# untitled.net
KiCad netlist of a schematic drawn in EAGLE
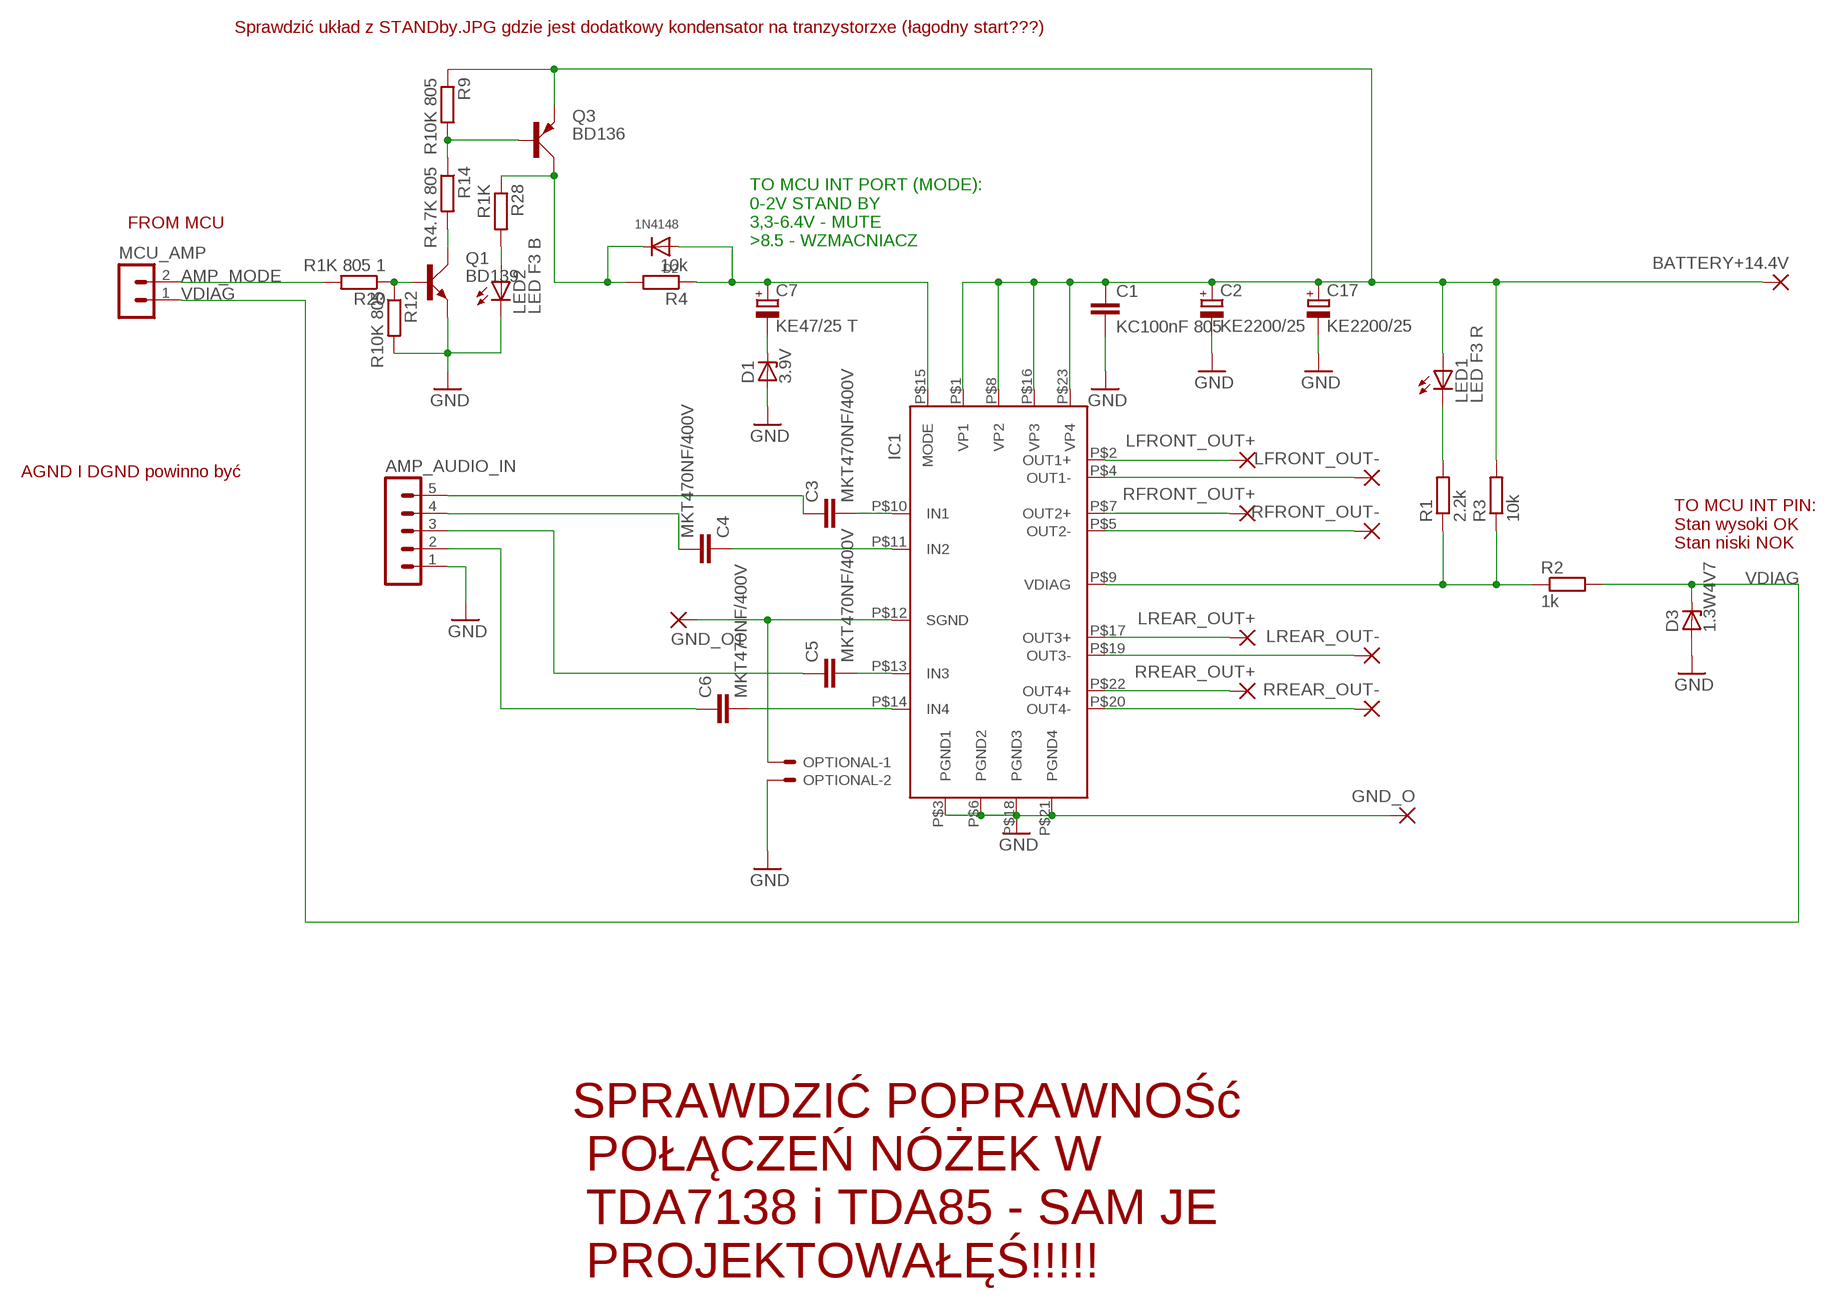
[diagram p0: schematic, sheet 1]

(export (version "E")
  (design (tool "Eeschema 10.0.6"))
  (components
    (comp (ref "AMP_AUDIO_IN")
      (value "MA05-1")
      (footprint "eagle-import:MA05-1")
      (fields (field (name "OC_FARNELL") "unknown") (field (name "OC_NEWARK") "unknown"))
      (libsource (lib "eagle-import") (part "MA05-1"))
    )
    (comp (ref "BATTERY+14.4V")
      (value "WIREPAD2,54/1,0")
      (footprint "eagle-import:2,54_1,0")
      (libsource (lib "eagle-import") (part "WIREPAD2,54/1,0"))
    )
    (comp (ref "C1")
      (value "KC100nF 805")
      (footprint "eagle-import:C0805")
      (libsource (lib "eagle-import") (part "C-EUC0805"))
    )
    (comp (ref "C2")
      (value "KE2200/25")
      (footprint "eagle-import:EB20D")
      (libsource (lib "eagle-import") (part "CPOL-EUE10-20"))
    )
    (comp (ref "C3")
      (value "MKT470NF/400V")
      (footprint "eagle-import:C025-024X044")
      (libsource (lib "eagle-import") (part "C-EU025-024X044"))
    )
    (comp (ref "C4")
      (value "MKT470NF/400V")
      (footprint "eagle-import:C025-024X044")
      (libsource (lib "eagle-import") (part "C-EU025-024X044"))
    )
    (comp (ref "C5")
      (value "MKT470NF/400V")
      (footprint "eagle-import:C025-024X044")
      (libsource (lib "eagle-import") (part "C-EU025-024X044"))
    )
    (comp (ref "C6")
      (value "MKT470NF/400V")
      (footprint "eagle-import:C025-024X044")
      (libsource (lib "eagle-import") (part "C-EU025-024X044"))
    )
    (comp (ref "C7")
      (value "KE47/25 T")
      (footprint "eagle-import:B45181A")
      (libsource (lib "eagle-import") (part "CPOL-EUB45181A"))
    )
    (comp (ref "C17")
      (value "KE2200/25")
      (footprint "eagle-import:EB20D")
      (libsource (lib "eagle-import") (part "CPOL-EUE10-20"))
    )
    (comp (ref "D1")
      (value "3.9V")
      (footprint "eagle-import:ZDIO-5")
      (libsource (lib "eagle-import") (part "ZENER-DIODEZD-5"))
    )
    (comp (ref "D2")
      (value "1N4148")
      (footprint "eagle-import:DO-1N4148")
      (libsource (lib "eagle-import") (part "DIODEDO-1N4148"))
    )
    (comp (ref "D3")
      (value "1.3W4V7")
      (footprint "eagle-import:ZDIO-5")
      (libsource (lib "eagle-import") (part "ZENER-DIODEZD-5"))
    )
    (comp (ref "GND_O")
      (value "WIREPAD2,54/1,0")
      (footprint "eagle-import:2,54_1,0")
      (libsource (lib "eagle-import") (part "WIREPAD2,54/1,0"))
    )
    (comp (ref "GND_O1")
      (value "WIREPAD2,54/1,0")
      (footprint "eagle-import:2,54_1,0")
      (libsource (lib "eagle-import") (part "WIREPAD2,54/1,0"))
    )
    (comp (ref "IC1")
      (value "TDA8571J")
      (footprint "eagle-import:SOT411-1")
      (libsource (lib "eagle-import") (part "TDA8571J"))
    )
    (comp (ref "LED1")
      (value "LED F3 R")
      (footprint "eagle-import:LED3MM")
      (libsource (lib "eagle-import") (part "LED3MM"))
    )
    (comp (ref "LED2")
      (value "LED F3 B")
      (footprint "eagle-import:LED3MM")
      (libsource (lib "eagle-import") (part "LED3MM"))
    )
    (comp (ref "LFRONT_OUT+")
      (value "WIREPAD2,54/1,0")
      (footprint "eagle-import:2,54_1,0")
      (libsource (lib "eagle-import") (part "WIREPAD2,54/1,0"))
    )
    (comp (ref "LFRONT_OUT-")
      (value "WIREPAD2,54/1,0")
      (footprint "eagle-import:2,54_1,0")
      (libsource (lib "eagle-import") (part "WIREPAD2,54/1,0"))
    )
    (comp (ref "LREAR_OUT+")
      (value "WIREPAD2,54/1,0")
      (footprint "eagle-import:2,54_1,0")
      (libsource (lib "eagle-import") (part "WIREPAD2,54/1,0"))
    )
    (comp (ref "LREAR_OUT-")
      (value "WIREPAD2,54/1,0")
      (footprint "eagle-import:2,54_1,0")
      (libsource (lib "eagle-import") (part "WIREPAD2,54/1,0"))
    )
    (comp (ref "MCU_AMP")
      (value "MA02-1")
      (footprint "eagle-import:MA02-1")
      (libsource (lib "eagle-import") (part "MA02-1"))
    )
    (comp (ref "OPTIONAL")
      (value "332-02")
      (footprint "eagle-import:332-02")
      (libsource (lib "eagle-import") (part "332-02"))
    )
    (comp (ref "Q1")
      (value "BD139")
      (footprint "eagle-import:TO126AV")
      (libsource (lib "eagle-import") (part "BD139"))
    )
    (comp (ref "Q3")
      (value "BD136")
      (footprint "eagle-import:TO126AV")
      (libsource (lib "eagle-import") (part "BD140"))
    )
    (comp (ref "R1")
      (value "2.2k")
      (footprint "eagle-import:0204_5")
      (libsource (lib "eagle-import") (part "R-EU_0204/5"))
    )
    (comp (ref "R2")
      (value "1k")
      (footprint "eagle-import:0204_5")
      (libsource (lib "eagle-import") (part "R-EU_0204/5"))
    )
    (comp (ref "R3")
      (value "10k")
      (footprint "eagle-import:0204_5")
      (libsource (lib "eagle-import") (part "R-EU_0204/5"))
    )
    (comp (ref "R4")
      (value "10k")
      (footprint "eagle-import:0204_5")
      (libsource (lib "eagle-import") (part "R-EU_0204/5"))
    )
    (comp (ref "R9")
      (value "R10K 805")
      (footprint "eagle-import:R0805")
      (libsource (lib "eagle-import") (part "R-EU_R0805"))
    )
    (comp (ref "R12")
      (value "R10K 805")
      (footprint "eagle-import:R0805")
      (libsource (lib "eagle-import") (part "R-EU_R0805"))
    )
    (comp (ref "R14")
      (value "R4.7K 805")
      (footprint "eagle-import:R0805")
      (libsource (lib "eagle-import") (part "R-EU_R0805"))
    )
    (comp (ref "R20")
      (value "R1K 805 1")
      (footprint "eagle-import:R0805")
      (libsource (lib "eagle-import") (part "R-EU_R0805"))
    )
    (comp (ref "R28")
      (value "R1K")
      (footprint "eagle-import:0204V")
      (libsource (lib "eagle-import") (part "R-EU_0204/2V"))
    )
    (comp (ref "RFRONT_OUT+")
      (value "WIREPAD2,54/1,0")
      (footprint "eagle-import:2,54_1,0")
      (libsource (lib "eagle-import") (part "WIREPAD2,54/1,0"))
    )
    (comp (ref "RFRONT_OUT-")
      (value "WIREPAD2,54/1,0")
      (footprint "eagle-import:2,54_1,0")
      (libsource (lib "eagle-import") (part "WIREPAD2,54/1,0"))
    )
    (comp (ref "RREAR_OUT+")
      (value "WIREPAD2,54/1,0")
      (footprint "eagle-import:2,54_1,0")
      (libsource (lib "eagle-import") (part "WIREPAD2,54/1,0"))
    )
    (comp (ref "RREAR_OUT-")
      (value "WIREPAD2,54/1,0")
      (footprint "eagle-import:2,54_1,0")
      (libsource (lib "eagle-import") (part "WIREPAD2,54/1,0"))
    )
  )
  (nets
    (net (code "1") (name "/AMP_MODE") (class "Default")
      (node (ref "MCU_AMP") (pin "2") (pinfunction "2_2") (pintype "passive"))
      (node (ref "R20") (pin "2") (pinfunction "2_2") (pintype "passive"))
    )
    (net (code "2") (name "/VDIAG") (class "Default")
      (node (ref "D3") (pin "C") (pinfunction "C_C") (pintype "passive"))
      (node (ref "MCU_AMP") (pin "1") (pinfunction "1_1") (pintype "passive"))
      (node (ref "R2") (pin "2") (pinfunction "2_2") (pintype "passive"))
    )
    (net (code "3") (name "GND") (class "Default")
      (node (ref "AMP_AUDIO_IN") (pin "1") (pinfunction "1_1") (pintype "passive"))
      (node (ref "C1") (pin "2") (pinfunction "2_2") (pintype "passive"))
      (node (ref "C17") (pin "-") (pinfunction "-_-") (pintype "passive"))
      (node (ref "C2") (pin "-") (pinfunction "-_-") (pintype "passive"))
      (node (ref "D1") (pin "A") (pinfunction "A_A") (pintype "passive"))
      (node (ref "D3") (pin "A") (pinfunction "A_A") (pintype "passive"))
      (node (ref "GND_O") (pin "1") (pinfunction "P_1") (pintype "passive"))
      (node (ref "IC1") (pin "P$18") (pinfunction "PGND3_P$18") (pintype "power_in"))
      (node (ref "IC1") (pin "P$21") (pinfunction "PGND4_P$21") (pintype "power_in"))
      (node (ref "IC1") (pin "P$3") (pinfunction "PGND1_P$3") (pintype "power_in"))
      (node (ref "IC1") (pin "P$6") (pinfunction "PGND2_P$6") (pintype "power_in"))
      (node (ref "LED2") (pin "K") (pinfunction "C_K") (pintype "passive"))
      (node (ref "OPTIONAL") (pin "2") (pinfunction "S_2") (pintype "passive"))
      (node (ref "Q1") (pin "E") (pinfunction "E_E") (pintype "passive"))
      (node (ref "R12") (pin "2") (pinfunction "2_2") (pintype "passive"))
    )
    (net (code "4") (name "Net-(AMP_AUDIO_IN-Pad2)") (class "Default")
      (node (ref "AMP_AUDIO_IN") (pin "2") (pinfunction "2_2") (pintype "passive"))
      (node (ref "C6") (pin "1") (pinfunction "1_1") (pintype "passive"))
    )
    (net (code "5") (name "Net-(AMP_AUDIO_IN-Pad3)") (class "Default")
      (node (ref "AMP_AUDIO_IN") (pin "3") (pinfunction "3_3") (pintype "passive"))
      (node (ref "C5") (pin "1") (pinfunction "1_1") (pintype "passive"))
    )
    (net (code "6") (name "Net-(AMP_AUDIO_IN-Pad4)") (class "Default")
      (node (ref "AMP_AUDIO_IN") (pin "4") (pinfunction "4_4") (pintype "passive"))
      (node (ref "C4") (pin "2") (pinfunction "2_2") (pintype "passive"))
    )
    (net (code "7") (name "Net-(AMP_AUDIO_IN-Pad5)") (class "Default")
      (node (ref "AMP_AUDIO_IN") (pin "5") (pinfunction "5_5") (pintype "passive"))
      (node (ref "C3") (pin "1") (pinfunction "1_1") (pintype "passive"))
    )
    (net (code "8") (name "Net-(BATTERY+14.4V-P)") (class "Default")
      (node (ref "BATTERY+14.4V") (pin "1") (pinfunction "P_1") (pintype "passive"))
      (node (ref "C1") (pin "1") (pinfunction "1_1") (pintype "passive"))
      (node (ref "C17") (pin "+") (pinfunction "+_+") (pintype "passive"))
      (node (ref "C2") (pin "+") (pinfunction "+_+") (pintype "passive"))
      (node (ref "IC1") (pin "P$1") (pinfunction "VP1_P$1") (pintype "power_in"))
      (node (ref "IC1") (pin "P$16") (pinfunction "VP3_P$16") (pintype "power_in"))
      (node (ref "IC1") (pin "P$23") (pinfunction "VP4_P$23") (pintype "power_in"))
      (node (ref "IC1") (pin "P$8") (pinfunction "VP2_P$8") (pintype "power_in"))
      (node (ref "LED1") (pin "A") (pinfunction "A_A") (pintype "passive"))
      (node (ref "Q3") (pin "E") (pinfunction "E_E") (pintype "passive"))
      (node (ref "R3") (pin "2") (pinfunction "2_2") (pintype "passive"))
      (node (ref "R9") (pin "1") (pinfunction "1_1") (pintype "passive"))
    )
    (net (code "9") (name "Net-(C7-Pad-)") (class "Default")
      (node (ref "C7") (pin "-") (pinfunction "-_-") (pintype "passive"))
      (node (ref "D1") (pin "C") (pinfunction "C_C") (pintype "passive"))
    )
    (net (code "10") (name "Net-(D2-PadC)") (class "Default")
      (node (ref "D2") (pin "C") (pinfunction "C_C") (pintype "passive"))
      (node (ref "Q3") (pin "C") (pinfunction "C_C") (pintype "passive"))
      (node (ref "R28") (pin "1") (pinfunction "1_1") (pintype "passive"))
      (node (ref "R4") (pin "2") (pinfunction "2_2") (pintype "passive"))
    )
    (net (code "11") (name "Net-(GND_O1-P)") (class "Default")
      (node (ref "GND_O1") (pin "1") (pinfunction "P_1") (pintype "passive"))
      (node (ref "IC1") (pin "P$12") (pinfunction "SGND_P$12") (pintype "power_in"))
      (node (ref "OPTIONAL") (pin "1") (pinfunction "S_1") (pintype "passive"))
    )
    (net (code "12") (name "Net-(IC1-IN1)") (class "Default")
      (node (ref "C3") (pin "2") (pinfunction "2_2") (pintype "passive"))
      (node (ref "IC1") (pin "P$10") (pinfunction "IN1_P$10") (pintype "input"))
    )
    (net (code "13") (name "Net-(IC1-IN2)") (class "Default")
      (node (ref "C4") (pin "1") (pinfunction "1_1") (pintype "passive"))
      (node (ref "IC1") (pin "P$11") (pinfunction "IN2_P$11") (pintype "input"))
    )
    (net (code "14") (name "Net-(IC1-IN3)") (class "Default")
      (node (ref "C5") (pin "2") (pinfunction "2_2") (pintype "passive"))
      (node (ref "IC1") (pin "P$13") (pinfunction "IN3_P$13") (pintype "input"))
    )
    (net (code "15") (name "Net-(IC1-IN4)") (class "Default")
      (node (ref "C6") (pin "2") (pinfunction "2_2") (pintype "passive"))
      (node (ref "IC1") (pin "P$14") (pinfunction "IN4_P$14") (pintype "input"))
    )
    (net (code "16") (name "Net-(IC1-MODE)") (class "Default")
      (node (ref "C7") (pin "+") (pinfunction "+_+") (pintype "passive"))
      (node (ref "D2") (pin "A") (pinfunction "A_A") (pintype "passive"))
      (node (ref "IC1") (pin "P$15") (pinfunction "MODE_P$15") (pintype "bidirectional"))
      (node (ref "R4") (pin "1") (pinfunction "1_1") (pintype "passive"))
    )
    (net (code "17") (name "Net-(IC1-OUT1+)") (class "Default")
      (node (ref "IC1") (pin "P$2") (pinfunction "OUT1+_P$2") (pintype "output"))
      (node (ref "LFRONT_OUT+") (pin "1") (pinfunction "P_1") (pintype "passive"))
    )
    (net (code "18") (name "Net-(IC1-OUT1-)") (class "Default")
      (node (ref "IC1") (pin "P$4") (pinfunction "OUT1-_P$4") (pintype "output"))
      (node (ref "LFRONT_OUT-") (pin "1") (pinfunction "P_1") (pintype "passive"))
    )
    (net (code "19") (name "Net-(IC1-OUT2+)") (class "Default")
      (node (ref "IC1") (pin "P$7") (pinfunction "OUT2+_P$7") (pintype "output"))
      (node (ref "RFRONT_OUT+") (pin "1") (pinfunction "P_1") (pintype "passive"))
    )
    (net (code "20") (name "Net-(IC1-OUT2-)") (class "Default")
      (node (ref "IC1") (pin "P$5") (pinfunction "OUT2-_P$5") (pintype "output"))
      (node (ref "RFRONT_OUT-") (pin "1") (pinfunction "P_1") (pintype "passive"))
    )
    (net (code "21") (name "Net-(IC1-OUT3+)") (class "Default")
      (node (ref "IC1") (pin "P$17") (pinfunction "OUT3+_P$17") (pintype "output"))
      (node (ref "LREAR_OUT+") (pin "1") (pinfunction "P_1") (pintype "passive"))
    )
    (net (code "22") (name "Net-(IC1-OUT3-)") (class "Default")
      (node (ref "IC1") (pin "P$19") (pinfunction "OUT3-_P$19") (pintype "output"))
      (node (ref "LREAR_OUT-") (pin "1") (pinfunction "P_1") (pintype "passive"))
    )
    (net (code "23") (name "Net-(IC1-OUT4+)") (class "Default")
      (node (ref "IC1") (pin "P$22") (pinfunction "OUT4+_P$22") (pintype "output"))
      (node (ref "RREAR_OUT+") (pin "1") (pinfunction "P_1") (pintype "passive"))
    )
    (net (code "24") (name "Net-(IC1-OUT4-)") (class "Default")
      (node (ref "IC1") (pin "P$20") (pinfunction "OUT4-_P$20") (pintype "output"))
      (node (ref "RREAR_OUT-") (pin "1") (pinfunction "P_1") (pintype "passive"))
    )
    (net (code "25") (name "Net-(IC1-VDIAG)") (class "Default")
      (node (ref "IC1") (pin "P$9") (pinfunction "VDIAG_P$9") (pintype "bidirectional"))
      (node (ref "R1") (pin "1") (pinfunction "1_1") (pintype "passive"))
      (node (ref "R2") (pin "1") (pinfunction "1_1") (pintype "passive"))
      (node (ref "R3") (pin "1") (pinfunction "1_1") (pintype "passive"))
    )
    (net (code "26") (name "Net-(LED1-C)") (class "Default")
      (node (ref "LED1") (pin "K") (pinfunction "C_K") (pintype "passive"))
      (node (ref "R1") (pin "2") (pinfunction "2_2") (pintype "passive"))
    )
    (net (code "27") (name "Net-(LED2-PadA)") (class "Default")
      (node (ref "LED2") (pin "A") (pinfunction "A_A") (pintype "passive"))
      (node (ref "R28") (pin "2") (pinfunction "2_2") (pintype "passive"))
    )
    (net (code "28") (name "Net-(Q1-PadB)") (class "Default")
      (node (ref "Q1") (pin "B") (pinfunction "B_B") (pintype "passive"))
      (node (ref "R12") (pin "1") (pinfunction "1_1") (pintype "passive"))
      (node (ref "R20") (pin "1") (pinfunction "1_1") (pintype "passive"))
    )
    (net (code "29") (name "Net-(Q1-PadC)") (class "Default")
      (node (ref "Q1") (pin "C") (pinfunction "C_C") (pintype "passive"))
      (node (ref "R14") (pin "2") (pinfunction "2_2") (pintype "passive"))
    )
    (net (code "30") (name "Net-(Q3-PadB)") (class "Default")
      (node (ref "Q3") (pin "B") (pinfunction "B_B") (pintype "passive"))
      (node (ref "R14") (pin "1") (pinfunction "1_1") (pintype "passive"))
      (node (ref "R9") (pin "2") (pinfunction "2_2") (pintype "passive"))
    )
  )
)
